# 2_4G.net
KiCad netlist of a schematic drawn in Altium Designer
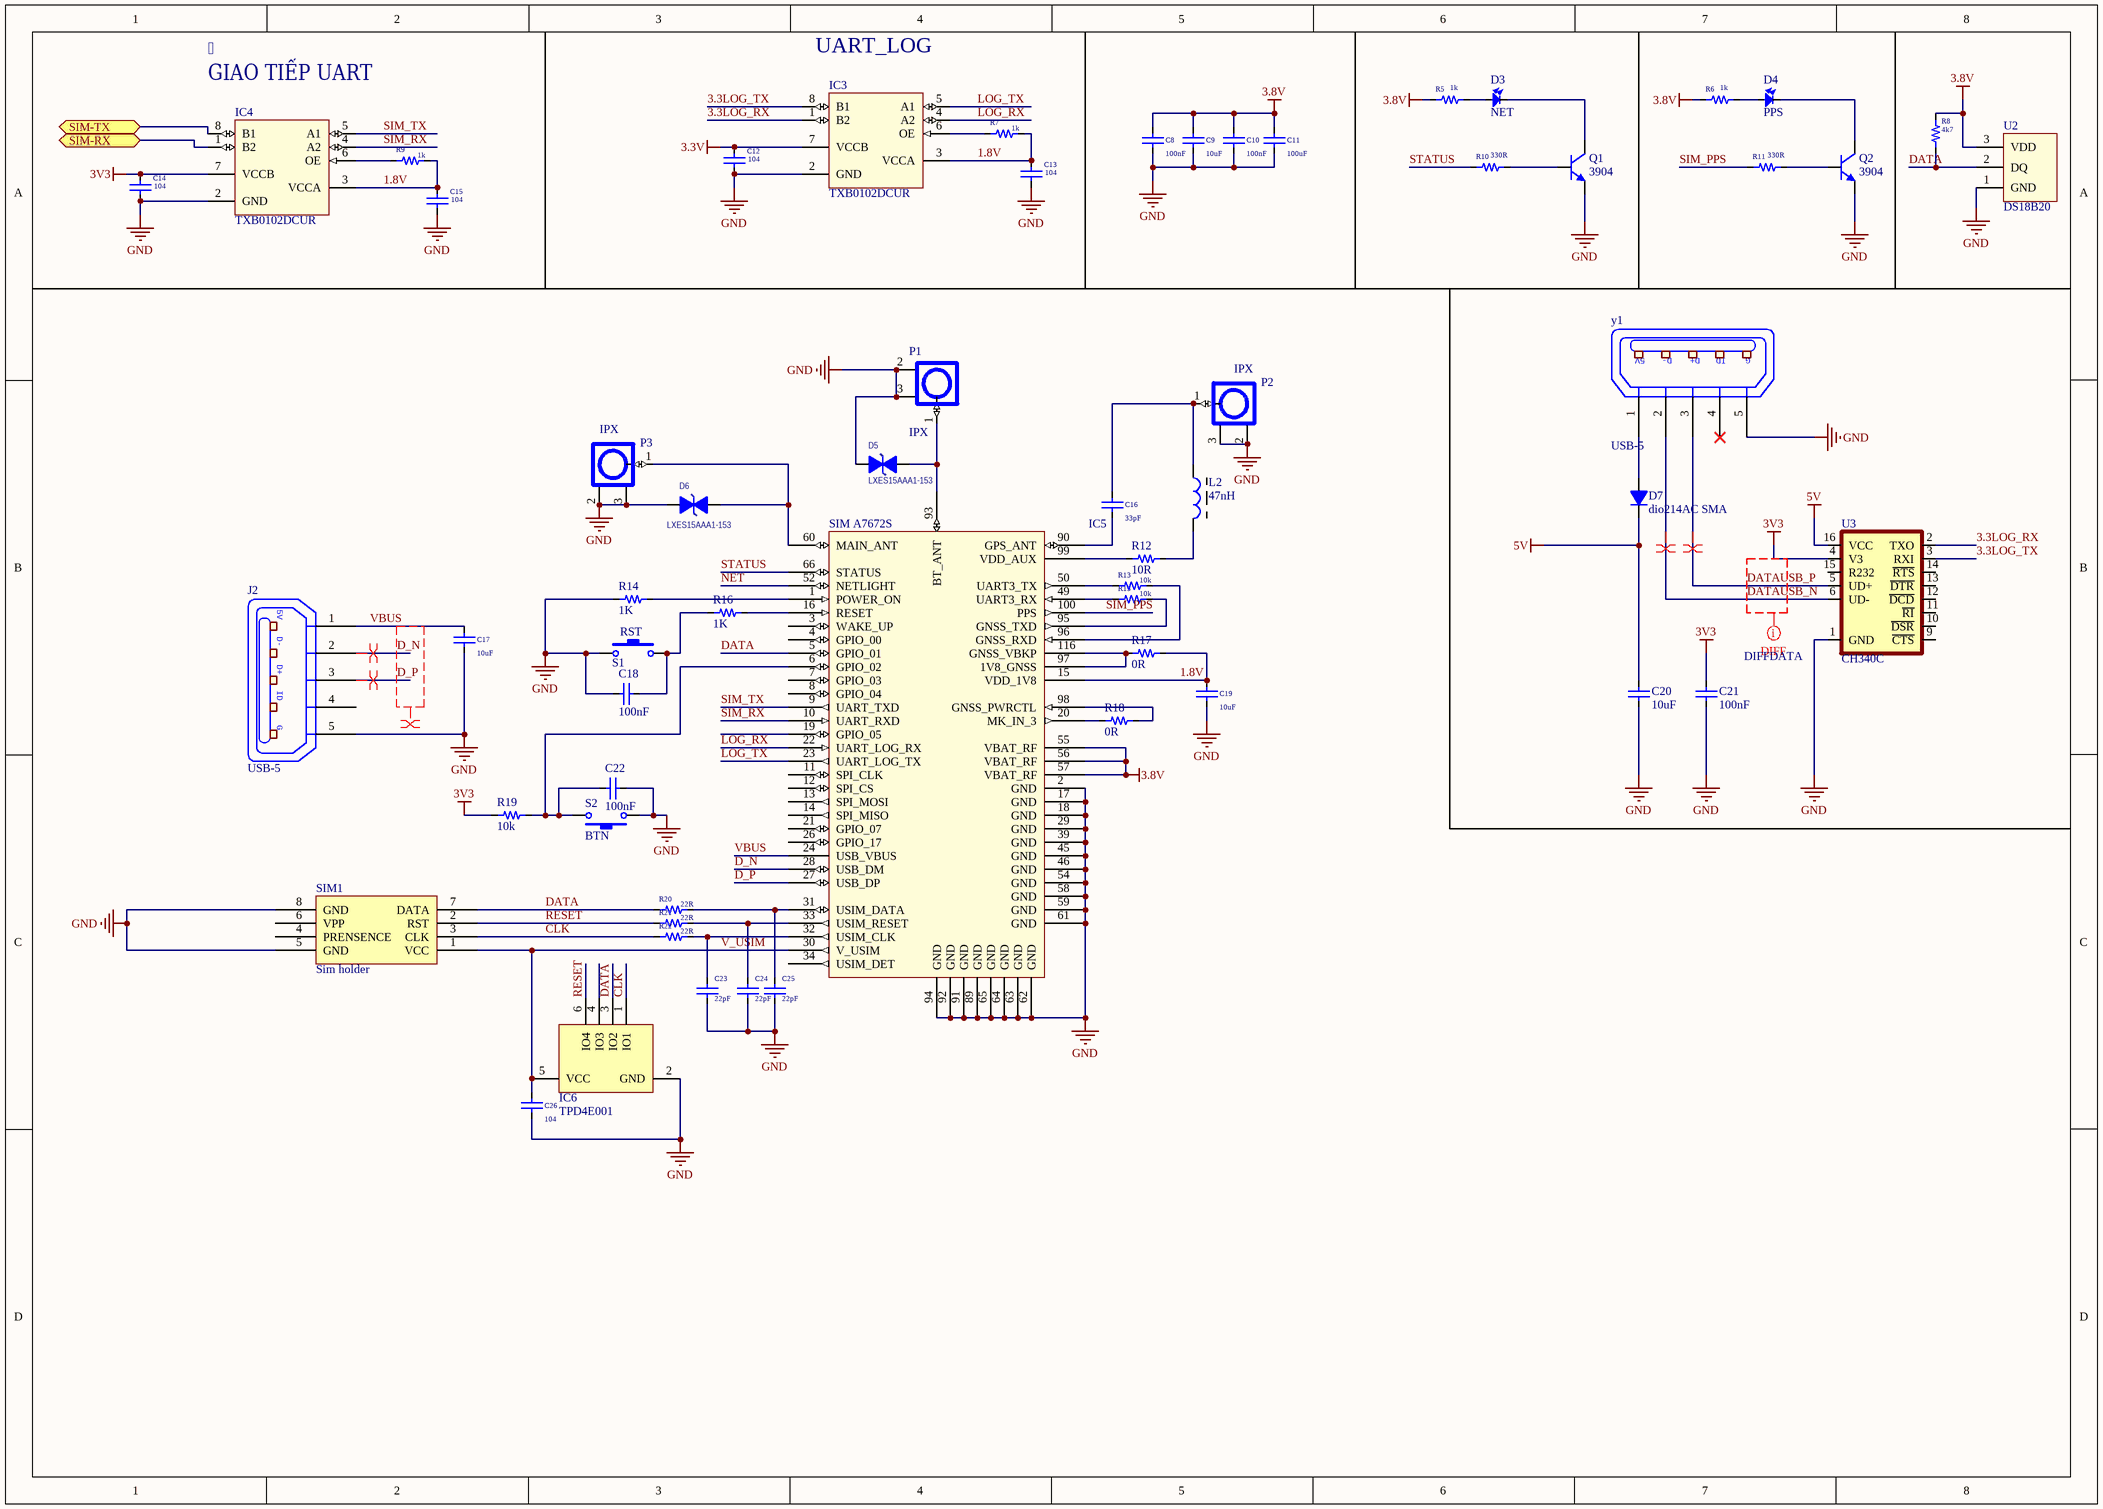
[diagram p0: 2.4G.SchDoc]

(export (version "E")
  (design (tool "Eeschema 10.0.6"))
  (components
    (comp (ref "C8")
      (value "100nF")
      (footprint "CAP_0805")
      (description "Capacitor")
      (fields (field (name "PUBLISHER") "Altium Limited"))
      (libsource (lib "My Library") (part "CapSMD"))
    )
    (comp (ref "C9")
      (value "10uF")
      (footprint "CAP_0805")
      (description "Capacitor")
      (fields (field (name "PUBLISHER") "Altium Limited"))
      (libsource (lib "My Library") (part "CapSMD"))
    )
    (comp (ref "C10")
      (value "100nF")
      (footprint "CAP_0805")
      (description "Capacitor")
      (fields (field (name "PUBLISHER") "Altium Limited"))
      (libsource (lib "My Library") (part "CapSMD"))
    )
    (comp (ref "C11")
      (value "100uF")
      (footprint "CAP_0805")
      (description "Capacitor")
      (fields (field (name "PUBLISHER") "Altium Limited"))
      (libsource (lib "My Library") (part "CapSMD"))
    )
    (comp (ref "C12")
      (value "104")
      (footprint "CAP_0805")
      (description "Capacitor")
      (fields (field (name "PUBLISHER") "Altium Limited"))
      (libsource (lib "My Library") (part "CapSMD"))
    )
    (comp (ref "C13")
      (value "104")
      (footprint "CAP_0805")
      (description "Capacitor")
      (fields (field (name "PUBLISHER") "Altium Limited"))
      (libsource (lib "My Library") (part "CapSMD"))
    )
    (comp (ref "C14")
      (value "104")
      (footprint "CAP_0805")
      (description "Capacitor")
      (fields (field (name "PUBLISHER") "Altium Limited"))
      (libsource (lib "My Library") (part "CapSMD"))
    )
    (comp (ref "C15")
      (value "104")
      (footprint "CAP_0805")
      (description "Capacitor")
      (fields (field (name "PUBLISHER") "Altium Limited"))
      (libsource (lib "My Library") (part "CapSMD"))
    )
    (comp (ref "C16")
      (value "33pF")
      (footprint "CAP_0805")
      (description "Capacitor")
      (fields (field (name "PUBLISHER") "Altium Limited"))
      (libsource (lib "My Library") (part "CapSMD"))
    )
    (comp (ref "C17")
      (value "10uF")
      (footprint "CAP_0603")
      (description "Capacitor")
      (fields (field (name "PUBLISHER") "Altium Limited"))
      (libsource (lib "My Library") (part "CapSMD"))
    )
    (comp (ref "C18")
      (value "100nF")
      (footprint "CAP_0805")
      (description "Capacitor")
      (fields (field (name "PUBLISHER") "Altium Limited"))
      (libsource (lib "My-Library") (part "CapSMD"))
    )
    (comp (ref "C19")
      (value "10uF")
      (footprint "CAP_0805")
      (description "Capacitor")
      (fields (field (name "PUBLISHER") "Altium Limited"))
      (libsource (lib "My Library") (part "CapSMD"))
    )
    (comp (ref "C20")
      (value "10uF")
      (footprint "CAP_0805")
      (description "Capacitor")
      (fields (field (name "PUBLISHER") "Altium Limited"))
      (libsource (lib "Main") (part "CapSMD"))
    )
    (comp (ref "C21")
      (value "100nF")
      (footprint "CAP_0402")
      (description "Capacitor")
      (fields (field (name "PUBLISHER") "Altium Limited"))
      (libsource (lib "Main") (part "CapSMD"))
    )
    (comp (ref "C22")
      (value "100nF")
      (footprint "CAP_0805")
      (description "Capacitor")
      (fields (field (name "PUBLISHER") "Altium Limited"))
      (libsource (lib "My-Library") (part "CapSMD"))
    )
    (comp (ref "C23")
      (value "22pF")
      (footprint "CAP_0805")
      (description "Capacitor")
      (fields (field (name "PUBLISHER") "Altium Limited"))
      (libsource (lib "My Library") (part "CapSMD"))
    )
    (comp (ref "C24")
      (value "22pF")
      (footprint "CAP_0805")
      (description "Capacitor")
      (fields (field (name "PUBLISHER") "Altium Limited"))
      (libsource (lib "My Library") (part "CapSMD"))
    )
    (comp (ref "C25")
      (value "22pF")
      (footprint "CAP_0805")
      (description "Capacitor")
      (fields (field (name "PUBLISHER") "Altium Limited"))
      (libsource (lib "My Library") (part "CapSMD"))
    )
    (comp (ref "C26")
      (value "104")
      (footprint "CAP_0805")
      (description "Capacitor")
      (fields (field (name "PUBLISHER") "Altium Limited"))
      (libsource (lib "My Library") (part "CapSMD"))
    )
    (comp (ref "D3")
      (value "NET")
      (footprint "LED-0805-Blue")
      (description "LED Single colour Green and Red")
      (libsource (lib "My Library") (part "LED"))
    )
    (comp (ref "D4")
      (value "PPS")
      (footprint "LED-0805-Blue")
      (description "LED Single colour Green and Red")
      (libsource (lib "My Library") (part "LED"))
    )
    (comp (ref "D5")
      (value "LXES15AAA1-153")
      (footprint "INDC1005X45")
      (description "TVS DIODE 4VWM 1005")
      (fields (field (name "MANUFACTURER") "Murata Electronics"))
      (libsource (lib "Anh_Trung") (part "TVS"))
    )
    (comp (ref "D6")
      (value "LXES15AAA1-153")
      (footprint "INDC1005X45")
      (description "TVS DIODE 4VWM 1005")
      (fields (field (name "MANUFACTURER") "Murata Electronics"))
      (libsource (lib "Anh_Trung") (part "TVS"))
    )
    (comp (ref "D7")
      (value "dio214AC SMA")
      (footprint "DIO-SMD-106")
      (description "Diode 1A")
      (libsource (lib "Main") (part "D1A"))
    )
    (comp (ref "IC3")
      (value "TXB0102DCUR")
      (footprint "SOP50P310X90-8N")
      (description "IC TRNSLTR BIDIRECTIONAL US8")
      (fields (field (name "MANUFACTURER") "Texas Instruments"))
      (libsource (lib "My Library") (part "TXB0102DCUR"))
    )
    (comp (ref "IC4")
      (value "TXB0102DCUR")
      (footprint "SOP50P310X90-8N")
      (description "IC TRNSLTR BIDIRECTIONAL US8")
      (fields (field (name "MANUFACTURER") "Texas Instruments"))
      (libsource (lib "Main") (part "TXB0102DCUR"))
    )
    (comp (ref "IC5")
      (value "SIM A7672S")
      (footprint "A7672S")
      (description "SIM A7672S-CAT-M1")
      (libsource (lib "My Library") (part "SIM A7672S"))
    )
    (comp (ref "IC6")
      (value "TPD4E001")
      (footprint "SOT23-6")
      (fields (field (name "MANUFACTURER") "Texas Instruments") (field (name "PART NUMBER") "TPD4E001RDBVR"))
      (libsource (lib "Main") (part "TPD4E001_1"))
    )
    (comp (ref "J2")
      (value "USB-5")
      (footprint "USB-M1")
      (fields (field (name "MANUFACTURER") "FCI"))
      (libsource (lib "SIM_devkit") (part "USB-5"))
    )
    (comp (ref "L2")
      (value "47nH")
      (footprint "Inductor_SMD")
      (description "FIXED IND 47NH 300MA 700MOHM SMD")
      (fields (field (name "MANUFACTURER") "Taiyo Yuden") (field (name "PART NUMBER") "HK160847NJ-T"))
      (libsource (lib "Anh_Trung") (part "Inductor Ferit"))
    )
    (comp (ref "P1")
      (value "IPX")
      (footprint "IPXS")
      (description "Antenna GSM GPS")
      (fields
        (field (name "MANUFACTURER") "TE Connectivity AMP Connectors")
        (field (name "PART NUMBER") "2334884-1")
      )
      (libsource (lib "Anh_Trung") (part "IPXSx66"))
    )
    (comp (ref "P2")
      (value "IPX")
      (footprint "IPXS")
      (description "Antenna GSM GPS")
      (fields
        (field (name "MANUFACTURER") "TE Connectivity AMP Connectors")
        (field (name "PART NUMBER") "2334884-1")
      )
      (libsource (lib "") (part "IPXSx66_1"))
    )
    (comp (ref "P3")
      (value "IPX")
      (footprint "IPXS")
      (description "Antenna GSM GPS")
      (fields
        (field (name "MANUFACTURER") "TE Connectivity AMP Connectors")
        (field (name "PART NUMBER") "2334884-1")
      )
      (libsource (lib "Anh_Trung") (part "IPXSx66"))
    )
    (comp (ref "Q1") (value "3904") (footprint "MMBT3904") (libsource (lib "My Library") (part "MMBT3904")))
    (comp (ref "Q2") (value "3904") (footprint "MMBT3904") (libsource (lib "My Library") (part "MMBT3904")))
    (comp (ref "R5")
      (value "1k")
      (footprint "RES-SMD-0805")
      (description "Resistor")
      (fields
        (field (name "MANUFACTURER") "Generic Components")
        (field (name "PUBLISHER") "Altium Hobart Technology Centre")
      )
      (libsource (lib "My Library") (part "Resistor - SMD"))
    )
    (comp (ref "R6")
      (value "1k")
      (footprint "RES-SMD-0805")
      (description "Resistor")
      (fields
        (field (name "MANUFACTURER") "Generic Components")
        (field (name "PUBLISHER") "Altium Hobart Technology Centre")
      )
      (libsource (lib "My Library") (part "Resistor - SMD"))
    )
    (comp (ref "R7")
      (value "1k")
      (footprint "RES-SMD-0805")
      (description "Resistor")
      (fields
        (field (name "MANUFACTURER") "Generic Components")
        (field (name "PUBLISHER") "Altium Hobart Technology Centre")
      )
      (libsource (lib "My Library") (part "Resistor - SMD"))
    )
    (comp (ref "R8")
      (value "4k7")
      (footprint "RES-SMD-0805")
      (description "Resistor")
      (fields
        (field (name "MANUFACTURER") "Generic Components")
        (field (name "PUBLISHER") "Altium Hobart Technology Centre")
      )
      (libsource (lib "My Library") (part "Resistor - SMD"))
    )
    (comp (ref "R9")
      (value "1k")
      (footprint "RES-SMD-0805")
      (description "Resistor")
      (fields
        (field (name "MANUFACTURER") "Generic Components")
        (field (name "PUBLISHER") "Altium Hobart Technology Centre")
      )
      (libsource (lib "My Library") (part "Resistor - SMD"))
    )
    (comp (ref "R10")
      (value "330R")
      (footprint "RES-SMD-0805")
      (description "Resistor")
      (fields
        (field (name "MANUFACTURER") "Generic Components")
        (field (name "PUBLISHER") "Altium Hobart Technology Centre")
      )
      (libsource (lib "My Library") (part "Resistor - SMD"))
    )
    (comp (ref "R11")
      (value "330R")
      (footprint "RES-SMD-0805")
      (description "Resistor")
      (fields
        (field (name "MANUFACTURER") "Generic Components")
        (field (name "PUBLISHER") "Altium Hobart Technology Centre")
      )
      (libsource (lib "My Library") (part "Resistor - SMD"))
    )
    (comp (ref "R12")
      (value "10R")
      (footprint "RES-SMD-0805")
      (description "Resistor")
      (fields
        (field (name "MANUFACTURER") "Generic Components")
        (field (name "PUBLISHER") "Altium Hobart Technology Centre")
      )
      (libsource (lib "My Library") (part "Resistor - SMD"))
    )
    (comp (ref "R13")
      (value "10k")
      (footprint "RES-SMD-0805")
      (description "Resistor")
      (fields
        (field (name "MANUFACTURER") "Generic Components")
        (field (name "PUBLISHER") "Altium Hobart Technology Centre")
      )
      (libsource (lib "My Library") (part "Resistor - SMD"))
    )
    (comp (ref "R14")
      (value "1K")
      (footprint "RES-SMD-0805")
      (description "Resistor")
      (fields
        (field (name "MANUFACTURER") "Generic Components")
        (field (name "PUBLISHER") "Altium Hobart Technology Centre")
      )
      (libsource (lib "My Library") (part "Resistor - SMD"))
    )
    (comp (ref "R15")
      (value "10k")
      (footprint "RES-SMD-0805")
      (description "Resistor")
      (fields
        (field (name "MANUFACTURER") "Generic Components")
        (field (name "PUBLISHER") "Altium Hobart Technology Centre")
      )
      (libsource (lib "My Library") (part "Resistor - SMD"))
    )
    (comp (ref "R16")
      (value "1K")
      (footprint "RES-SMD-0805")
      (description "Resistor")
      (fields
        (field (name "MANUFACTURER") "Generic Components")
        (field (name "PUBLISHER") "Altium Hobart Technology Centre")
      )
      (libsource (lib "My Library") (part "Resistor - SMD"))
    )
    (comp (ref "R17")
      (value "0R")
      (footprint "RES-SMD-0805")
      (description "Resistor")
      (fields
        (field (name "MANUFACTURER") "Generic Components")
        (field (name "PUBLISHER") "Altium Hobart Technology Centre")
      )
      (libsource (lib "My Library") (part "Resistor - SMD"))
    )
    (comp (ref "R18")
      (value "0R")
      (footprint "RES-SMD-0805")
      (description "Resistor")
      (fields
        (field (name "MANUFACTURER") "Generic Components")
        (field (name "PUBLISHER") "Altium Hobart Technology Centre")
      )
      (libsource (lib "My Library") (part "Resistor - SMD"))
    )
    (comp (ref "R19")
      (value "10k")
      (footprint "RES-SMD-0805")
      (description "Resistor")
      (fields
        (field (name "MANUFACTURER") "Generic Components")
        (field (name "PUBLISHER") "Altium Hobart Technology Centre")
      )
      (libsource (lib "My Library") (part "Resistor - SMD"))
    )
    (comp (ref "R20")
      (value "22R")
      (footprint "RES-SMD-0805")
      (description "Resistor")
      (fields
        (field (name "MANUFACTURER") "Generic Components")
        (field (name "PUBLISHER") "Altium Hobart Technology Centre")
      )
      (libsource (lib "My Library") (part "Resistor - SMD"))
    )
    (comp (ref "R21")
      (value "22R")
      (footprint "RES-SMD-0805")
      (description "Resistor")
      (fields
        (field (name "MANUFACTURER") "Generic Components")
        (field (name "PUBLISHER") "Altium Hobart Technology Centre")
      )
      (libsource (lib "My Library") (part "Resistor - SMD"))
    )
    (comp (ref "R22")
      (value "22R")
      (footprint "RES-SMD-0805")
      (description "Resistor")
      (fields
        (field (name "MANUFACTURER") "Generic Components")
        (field (name "PUBLISHER") "Altium Hobart Technology Centre")
      )
      (libsource (lib "My Library") (part "Resistor - SMD"))
    )
    (comp (ref "S1")
      (value "RST")
      (footprint "SW-SMD")
      (description "Switch")
      (fields (field (name "PUBLISHER") "Altium Limited"))
      (libsource (lib "My Library") (part "SW-SMD"))
    )
    (comp (ref "S2")
      (value "BTN")
      (footprint "SW-SMD")
      (description "Switch")
      (fields (field (name "PUBLISHER") "Altium Limited"))
      (libsource (lib "My Library") (part "SW-SMD"))
    )
    (comp (ref "SIM1")
      (value "Sim holder")
      (footprint "SIM_MicroSIM 6P Flip")
      (libsource (lib "My-Library") (part "SIM_MicroSim"))
    )
    (comp (ref "U2")
      (value "DS18B20")
      (footprint "QTO-92A")
      (description "High Precision  1-Wire® Digital Thermometer")
      (libsource (lib "Main") (part "DS18B20"))
    )
    (comp (ref "U3")
      (value "CH340C")
      (footprint "SOP-16")
      (description "USB to serial chip CH340")
      (fields (field (name "MF") "WCH"))
      (libsource (lib "Main") (part "CH340C"))
    )
    (comp (ref "y1")
      (value "USB-5")
      (footprint "USB-M1")
      (fields (field (name "MANUFACTURER") "FCI"))
      (libsource (lib "") (part "USB-5_1"))
    )
  )
  (nets
    (net (code "1") (name "/1.8V") (class "Default")
      (node (ref "C13") (pin "2") (pinfunction "2_2") (pintype "passive"))
      (node (ref "C15") (pin "2") (pinfunction "2_2") (pintype "passive"))
      (node (ref "C19") (pin "2") (pinfunction "2_2") (pintype "passive"))
      (node (ref "IC3") (pin "3") (pinfunction "VCCA_3") (pintype "power_in"))
      (node (ref "IC4") (pin "3") (pinfunction "VCCA_3") (pintype "power_in"))
      (node (ref "IC5") (pin "15") (pinfunction "VDD_1V8_15") (pintype "passive"))
      (node (ref "R17") (pin "2") (pinfunction "2_2") (pintype "passive"))
      (node (ref "R7") (pin "1") (pinfunction "1_1") (pintype "passive"))
      (node (ref "R9") (pin "1") (pinfunction "1_1") (pintype "passive"))
    )
    (net (code "2") (name "/3.3LOG_RX") (class "Default")
      (node (ref "IC3") (pin "1") (pinfunction "B2_1") (pintype "bidirectional"))
      (node (ref "U3") (pin "2") (pinfunction "TXO_2") (pintype "bidirectional"))
    )
    (net (code "3") (name "/3.3LOG_TX") (class "Default")
      (node (ref "IC3") (pin "8") (pinfunction "B1_8") (pintype "bidirectional"))
      (node (ref "U3") (pin "3") (pinfunction "RXI_3") (pintype "bidirectional"))
    )
    (net (code "4") (name "/CLK") (class "Default")
      (node (ref "IC6") (pin "1") (pinfunction "IO1_1") (pintype "passive"))
      (node (ref "R22") (pin "2") (pinfunction "2_2") (pintype "passive"))
      (node (ref "SIM1") (pin "3") (pinfunction "CLK_3") (pintype "passive"))
    )
    (net (code "5") (name "/DATA") (class "Default")
      (node (ref "IC5") (pin "5") (pinfunction "GPIO_01_5") (pintype "bidirectional"))
      (node (ref "IC6") (pin "3") (pinfunction "IO2_3") (pintype "passive"))
      (node (ref "R20") (pin "2") (pinfunction "2_2") (pintype "passive"))
      (node (ref "R8") (pin "2") (pinfunction "2_2") (pintype "passive"))
      (node (ref "SIM1") (pin "7") (pinfunction "DATA_7") (pintype "passive"))
      (node (ref "U2") (pin "2") (pinfunction "DQ_2") (pintype "passive"))
    )
    (net (code "6") (name "/DATAUSB_N") (class "Default")
      (node (ref "U3") (pin "6") (pinfunction "UD-_6") (pintype "bidirectional"))
      (node (ref "y1") (pin "2") (pinfunction "P2_2") (pintype "passive"))
    )
    (net (code "7") (name "/DATAUSB_P") (class "Default")
      (node (ref "U3") (pin "5") (pinfunction "UD+_5") (pintype "bidirectional"))
      (node (ref "y1") (pin "3") (pinfunction "P3_3") (pintype "passive"))
    )
    (net (code "8") (name "/D_N") (class "Default")
      (node (ref "IC5") (pin "28") (pinfunction "USB_DM_28") (pintype "bidirectional"))
      (node (ref "J2") (pin "2") (pinfunction "P2_2") (pintype "passive"))
    )
    (net (code "9") (name "/D_P") (class "Default")
      (node (ref "IC5") (pin "27") (pinfunction "USB_DP_27") (pintype "bidirectional"))
      (node (ref "J2") (pin "3") (pinfunction "P3_3") (pintype "passive"))
    )
    (net (code "10") (name "/LOG_RX") (class "Default")
      (node (ref "IC3") (pin "4") (pinfunction "A2_4") (pintype "bidirectional"))
      (node (ref "IC5") (pin "22") (pinfunction "UART_LOG_RX_22") (pintype "input"))
    )
    (net (code "11") (name "/LOG_TX") (class "Default")
      (node (ref "IC3") (pin "5") (pinfunction "A1_5") (pintype "bidirectional"))
      (node (ref "IC5") (pin "23") (pinfunction "UART_LOG_TX_23") (pintype "output"))
    )
    (net (code "12") (name "/NET") (class "Default")
      (node (ref "IC5") (pin "52") (pinfunction "NETLIGHT_52") (pintype "bidirectional"))
    )
    (net (code "13") (name "/RESET") (class "Default")
      (node (ref "IC6") (pin "6") (pinfunction "IO4_6") (pintype "passive"))
      (node (ref "R21") (pin "2") (pinfunction "2_2") (pintype "passive"))
      (node (ref "SIM1") (pin "2") (pinfunction "RST_2") (pintype "passive"))
    )
    (net (code "14") (name "/SIM-RX") (class "Default")
      (node (ref "IC4") (pin "1") (pinfunction "B2_1") (pintype "bidirectional"))
    )
    (net (code "15") (name "/SIM-TX") (class "Default")
      (node (ref "IC4") (pin "8") (pinfunction "B1_8") (pintype "bidirectional"))
    )
    (net (code "16") (name "/SIM_PPS") (class "Default")
      (node (ref "IC5") (pin "100") (pinfunction "PPS_100") (pintype "output"))
      (node (ref "R11") (pin "2") (pinfunction "2_2") (pintype "passive"))
    )
    (net (code "17") (name "/SIM_RX") (class "Default")
      (node (ref "IC4") (pin "4") (pinfunction "A2_4") (pintype "bidirectional"))
      (node (ref "IC5") (pin "10") (pinfunction "UART_RXD_10") (pintype "input"))
    )
    (net (code "18") (name "/SIM_TX") (class "Default")
      (node (ref "IC4") (pin "5") (pinfunction "A1_5") (pintype "bidirectional"))
      (node (ref "IC5") (pin "9") (pinfunction "UART_TXD_9") (pintype "output"))
    )
    (net (code "19") (name "/STATUS") (class "Default")
      (node (ref "IC5") (pin "66") (pinfunction "STATUS_66") (pintype "bidirectional"))
      (node (ref "R10") (pin "2") (pinfunction "2_2") (pintype "passive"))
    )
    (net (code "20") (name "/VBUS") (class "Default")
      (node (ref "C17") (pin "2") (pinfunction "2_2") (pintype "passive"))
      (node (ref "IC5") (pin "24") (pinfunction "USB_VBUS_24") (pintype "passive"))
      (node (ref "J2") (pin "1") (pinfunction "P1_1") (pintype "passive"))
    )
    (net (code "21") (name "/V_USIM") (class "Default")
      (node (ref "C26") (pin "2") (pinfunction "2_2") (pintype "passive"))
      (node (ref "IC5") (pin "30") (pinfunction "V_USIM_30") (pintype "output"))
      (node (ref "IC6") (pin "5") (pinfunction "VCC_5") (pintype "passive"))
      (node (ref "SIM1") (pin "1") (pinfunction "VCC_1") (pintype "passive"))
    )
    (net (code "22") (name "3.3V") (class "Default")
      (node (ref "C12") (pin "2") (pinfunction "2_2") (pintype "passive"))
      (node (ref "IC3") (pin "7") (pinfunction "VCCB_7") (pintype "power_in"))
    )
    (net (code "23") (name "3.8V") (class "Default")
      (node (ref "C10") (pin "2") (pinfunction "2_2") (pintype "passive"))
      (node (ref "C11") (pin "2") (pinfunction "2_2") (pintype "passive"))
      (node (ref "C8") (pin "2") (pinfunction "2_2") (pintype "passive"))
      (node (ref "C9") (pin "2") (pinfunction "2_2") (pintype "passive"))
      (node (ref "IC5") (pin "55") (pinfunction "VBAT_RF_55") (pintype "passive"))
      (node (ref "IC5") (pin "56") (pinfunction "VBAT_RF_56") (pintype "passive"))
      (node (ref "IC5") (pin "57") (pinfunction "VBAT_RF_57") (pintype "passive"))
      (node (ref "R5") (pin "2") (pinfunction "2_2") (pintype "passive"))
      (node (ref "R6") (pin "2") (pinfunction "2_2") (pintype "passive"))
      (node (ref "R8") (pin "1") (pinfunction "1_1") (pintype "passive"))
      (node (ref "U2") (pin "3") (pinfunction "VDD_3") (pintype "passive"))
    )
    (net (code "24") (name "3V3") (class "Default")
      (node (ref "C14") (pin "2") (pinfunction "2_2") (pintype "passive"))
      (node (ref "C21") (pin "1") (pinfunction "1_1") (pintype "passive"))
      (node (ref "IC4") (pin "7") (pinfunction "VCCB_7") (pintype "power_in"))
      (node (ref "R19") (pin "1") (pinfunction "1_1") (pintype "passive"))
      (node (ref "U3") (pin "4") (pinfunction "V3_4") (pintype "bidirectional"))
    )
    (net (code "25") (name "5V") (class "Default")
      (node (ref "C20") (pin "1") (pinfunction "1_1") (pintype "passive"))
      (node (ref "D7") (pin "2") (pinfunction "K_2") (pintype "passive"))
      (node (ref "U3") (pin "16") (pinfunction "VCC_16") (pintype "bidirectional"))
    )
    (net (code "26") (name "GND") (class "Default")
      (node (ref "C10") (pin "1") (pinfunction "1_1") (pintype "passive"))
      (node (ref "C11") (pin "1") (pinfunction "1_1") (pintype "passive"))
      (node (ref "C12") (pin "1") (pinfunction "1_1") (pintype "passive"))
      (node (ref "C13") (pin "1") (pinfunction "1_1") (pintype "passive"))
      (node (ref "C14") (pin "1") (pinfunction "1_1") (pintype "passive"))
      (node (ref "C15") (pin "1") (pinfunction "1_1") (pintype "passive"))
      (node (ref "C17") (pin "1") (pinfunction "1_1") (pintype "passive"))
      (node (ref "C18") (pin "1") (pinfunction "1_1") (pintype "passive"))
      (node (ref "C19") (pin "1") (pinfunction "1_1") (pintype "passive"))
      (node (ref "C20") (pin "2") (pinfunction "2_2") (pintype "passive"))
      (node (ref "C21") (pin "2") (pinfunction "2_2") (pintype "passive"))
      (node (ref "C22") (pin "2") (pinfunction "2_2") (pintype "passive"))
      (node (ref "C23") (pin "1") (pinfunction "1_1") (pintype "passive"))
      (node (ref "C24") (pin "1") (pinfunction "1_1") (pintype "passive"))
      (node (ref "C25") (pin "1") (pinfunction "1_1") (pintype "passive"))
      (node (ref "C26") (pin "1") (pinfunction "1_1") (pintype "passive"))
      (node (ref "C8") (pin "1") (pinfunction "1_1") (pintype "passive"))
      (node (ref "C9") (pin "1") (pinfunction "1_1") (pintype "passive"))
      (node (ref "D5") (pin "2") (pinfunction "K_2") (pintype "passive"))
      (node (ref "D6") (pin "2") (pinfunction "K_2") (pintype "passive"))
      (node (ref "IC3") (pin "2") (pinfunction "GND_2") (pintype "power_in"))
      (node (ref "IC4") (pin "2") (pinfunction "GND_2") (pintype "power_in"))
      (node (ref "IC5") (pin "17") (pinfunction "GND_17") (pintype "passive"))
      (node (ref "IC5") (pin "18") (pinfunction "GND_18") (pintype "passive"))
      (node (ref "IC5") (pin "2") (pinfunction "GND_2") (pintype "passive"))
      (node (ref "IC5") (pin "29") (pinfunction "GND_29") (pintype "passive"))
      (node (ref "IC5") (pin "39") (pinfunction "GND_39") (pintype "passive"))
      (node (ref "IC5") (pin "45") (pinfunction "GND_45") (pintype "passive"))
      (node (ref "IC5") (pin "46") (pinfunction "GND_46") (pintype "passive"))
      (node (ref "IC5") (pin "54") (pinfunction "GND_54") (pintype "passive"))
      (node (ref "IC5") (pin "58") (pinfunction "GND_58") (pintype "passive"))
      (node (ref "IC5") (pin "59") (pinfunction "GND_59") (pintype "passive"))
      (node (ref "IC5") (pin "61") (pinfunction "GND_61") (pintype "passive"))
      (node (ref "IC5") (pin "62") (pinfunction "GND_62") (pintype "passive"))
      (node (ref "IC5") (pin "63") (pinfunction "GND_63") (pintype "passive"))
      (node (ref "IC5") (pin "64") (pinfunction "GND_64") (pintype "passive"))
      (node (ref "IC5") (pin "65") (pinfunction "GND_65") (pintype "passive"))
      (node (ref "IC5") (pin "89") (pinfunction "GND_89") (pintype "passive"))
      (node (ref "IC5") (pin "91") (pinfunction "GND_91") (pintype "passive"))
      (node (ref "IC5") (pin "92") (pinfunction "GND_92") (pintype "passive"))
      (node (ref "IC5") (pin "94") (pinfunction "GND_94") (pintype "passive"))
      (node (ref "IC6") (pin "2") (pinfunction "GND_2") (pintype "passive"))
      (node (ref "J2") (pin "5") (pinfunction "P5_5") (pintype "passive"))
      (node (ref "P1") (pin "2") (pintype "passive"))
      (node (ref "P1") (pin "3") (pintype "passive"))
      (node (ref "P2") (pin "2") (pintype "passive"))
      (node (ref "P2") (pin "3") (pintype "passive"))
      (node (ref "P3") (pin "2") (pintype "passive"))
      (node (ref "P3") (pin "3") (pintype "passive"))
      (node (ref "Q1") (pin "2") (pinfunction "E_2") (pintype "passive"))
      (node (ref "Q2") (pin "2") (pinfunction "E_2") (pintype "passive"))
      (node (ref "R14") (pin "1") (pinfunction "1_1") (pintype "passive"))
      (node (ref "S1") (pin "1") (pinfunction "1_1") (pintype "passive"))
      (node (ref "S2") (pin "1") (pinfunction "1_1") (pintype "passive"))
      (node (ref "SIM1") (pin "5") (pinfunction "GND_5") (pintype "passive"))
      (node (ref "SIM1") (pin "8") (pinfunction "GND_8") (pintype "passive"))
      (node (ref "U2") (pin "1") (pinfunction "GND_1") (pintype "passive"))
      (node (ref "U3") (pin "1") (pinfunction "GND_1") (pintype "bidirectional"))
      (node (ref "y1") (pin "5") (pinfunction "P5_5") (pintype "passive"))
    )
    (net (code "27") (name "Net-(C16-Pad2)") (class "Default")
      (node (ref "C16") (pin "2") (pinfunction "2_2") (pintype "passive"))
      (node (ref "L2") (pin "1") (pinfunction "1_1") (pintype "passive"))
      (node (ref "P2") (pin "1") (pintype "bidirectional"))
    )
    (net (code "28") (name "Net-(C18-Pad2)") (class "Default")
      (node (ref "C18") (pin "2") (pinfunction "2_2") (pintype "passive"))
      (node (ref "R16") (pin "1") (pinfunction "1_1") (pintype "passive"))
      (node (ref "S1") (pin "2") (pinfunction "2_2") (pintype "passive"))
    )
    (net (code "29") (name "Net-(D3-Pad1)") (class "Default")
      (node (ref "D3") (pin "1") (pinfunction "1_1") (pintype "passive"))
      (node (ref "R5") (pin "1") (pinfunction "1_1") (pintype "passive"))
    )
    (net (code "30") (name "Net-(D4-Pad1)") (class "Default")
      (node (ref "D4") (pin "1") (pinfunction "1_1") (pintype "passive"))
      (node (ref "R6") (pin "1") (pinfunction "1_1") (pintype "passive"))
    )
    (net (code "31") (name "Net-(D5-A)") (class "Default")
      (node (ref "D5") (pin "1") (pinfunction "A_1") (pintype "passive"))
      (node (ref "IC5") (pin "93") (pinfunction "BT_ANT_93") (pintype "bidirectional"))
      (node (ref "P1") (pin "1") (pintype "bidirectional"))
    )
    (net (code "32") (name "Net-(D6-A)") (class "Default")
      (node (ref "D6") (pin "1") (pinfunction "A_1") (pintype "passive"))
      (node (ref "IC5") (pin "60") (pinfunction "MAIN_ANT_60") (pintype "bidirectional"))
      (node (ref "P3") (pin "1") (pintype "bidirectional"))
    )
    (net (code "33") (name "Net-(D7-A)") (class "Default")
      (node (ref "D7") (pin "1") (pinfunction "A_1") (pintype "passive"))
      (node (ref "y1") (pin "1") (pinfunction "P1_1") (pintype "passive"))
    )
    (net (code "34") (name "Net-(IC3-OE)") (class "Default")
      (node (ref "IC3") (pin "6") (pinfunction "OE_6") (pintype "input"))
      (node (ref "R7") (pin "2") (pinfunction "2_2") (pintype "passive"))
    )
    (net (code "35") (name "Net-(IC4-OE)") (class "Default")
      (node (ref "IC4") (pin "6") (pinfunction "OE_6") (pintype "input"))
      (node (ref "R9") (pin "2") (pinfunction "2_2") (pintype "passive"))
    )
    (net (code "36") (name "Net-(IC5-1V8_GNSS)") (class "Default")
      (node (ref "IC5") (pin "116") (pinfunction "GNSS_VBKP_116") (pintype "passive"))
      (node (ref "IC5") (pin "97") (pinfunction "1V8_GNSS_97") (pintype "passive"))
      (node (ref "R17") (pin "1") (pinfunction "1_1") (pintype "passive"))
    )
    (net (code "37") (name "Net-(IC5-GNSS_PWRCTL)") (class "Default")
      (node (ref "IC5") (pin "98") (pinfunction "GNSS_PWRCTL_98") (pintype "input"))
      (node (ref "R18") (pin "2") (pinfunction "2_2") (pintype "passive"))
    )
    (net (code "38") (name "Net-(IC5-GNSS_RXD)") (class "Default")
      (node (ref "IC5") (pin "96") (pinfunction "GNSS_RXD_96") (pintype "input"))
      (node (ref "R13") (pin "1") (pinfunction "1_1") (pintype "passive"))
    )
    (net (code "39") (name "Net-(IC5-GNSS_TXD)") (class "Default")
      (node (ref "IC5") (pin "95") (pinfunction "GNSS_TXD_95") (pintype "output"))
      (node (ref "R15") (pin "1") (pinfunction "1_1") (pintype "passive"))
    )
    (net (code "40") (name "Net-(IC5-GPIO_02)") (class "Default")
      (node (ref "C22") (pin "1") (pinfunction "1_1") (pintype "passive"))
      (node (ref "IC5") (pin "6") (pinfunction "GPIO_02_6") (pintype "bidirectional"))
      (node (ref "R19") (pin "2") (pinfunction "2_2") (pintype "passive"))
      (node (ref "S2") (pin "2") (pinfunction "2_2") (pintype "passive"))
    )
    (net (code "41") (name "Net-(IC5-GPS_ANT)") (class "Default")
      (node (ref "C16") (pin "1") (pinfunction "1_1") (pintype "passive"))
      (node (ref "IC5") (pin "90") (pinfunction "GPS_ANT_90") (pintype "bidirectional"))
    )
    (net (code "42") (name "Net-(IC5-MK_IN_3)") (class "Default")
      (node (ref "IC5") (pin "20") (pinfunction "MK_IN_3_20") (pintype "output"))
      (node (ref "R18") (pin "1") (pinfunction "1_1") (pintype "passive"))
    )
    (net (code "43") (name "Net-(IC5-POWER_ON)") (class "Default")
      (node (ref "IC5") (pin "1") (pinfunction "POWER_ON_1") (pintype "input"))
      (node (ref "R14") (pin "2") (pinfunction "2_2") (pintype "passive"))
    )
    (net (code "44") (name "Net-(IC5-RESET)") (class "Default")
      (node (ref "IC5") (pin "16") (pinfunction "RESET_16") (pintype "input"))
      (node (ref "R16") (pin "2") (pinfunction "2_2") (pintype "passive"))
    )
    (net (code "45") (name "Net-(IC5-UART3_RX)") (class "Default")
      (node (ref "IC5") (pin "49") (pinfunction "UART3_RX_49") (pintype "input"))
      (node (ref "R15") (pin "2") (pinfunction "2_2") (pintype "passive"))
    )
    (net (code "46") (name "Net-(IC5-UART3_TX)") (class "Default")
      (node (ref "IC5") (pin "50") (pinfunction "UART3_TX_50") (pintype "output"))
      (node (ref "R13") (pin "2") (pinfunction "2_2") (pintype "passive"))
    )
    (net (code "47") (name "Net-(IC5-USIM_CLK)") (class "Default")
      (node (ref "C23") (pin "2") (pinfunction "2_2") (pintype "passive"))
      (node (ref "IC5") (pin "32") (pinfunction "USIM_CLK_32") (pintype "output"))
      (node (ref "R22") (pin "1") (pinfunction "1_1") (pintype "passive"))
    )
    (net (code "48") (name "Net-(IC5-USIM_DATA)") (class "Default")
      (node (ref "C25") (pin "2") (pinfunction "2_2") (pintype "passive"))
      (node (ref "IC5") (pin "31") (pinfunction "USIM_DATA_31") (pintype "bidirectional"))
      (node (ref "R20") (pin "1") (pinfunction "1_1") (pintype "passive"))
    )
    (net (code "49") (name "Net-(IC5-USIM_RESET)") (class "Default")
      (node (ref "C24") (pin "2") (pinfunction "2_2") (pintype "passive"))
      (node (ref "IC5") (pin "33") (pinfunction "USIM_RESET_33") (pintype "output"))
      (node (ref "R21") (pin "1") (pinfunction "1_1") (pintype "passive"))
    )
    (net (code "50") (name "Net-(IC5-VDD_AUX)") (class "Default")
      (node (ref "IC5") (pin "99") (pinfunction "VDD_AUX_99") (pintype "passive"))
      (node (ref "R12") (pin "1") (pinfunction "1_1") (pintype "passive"))
    )
    (net (code "51") (name "Net-(L2-Pad2)") (class "Default")
      (node (ref "L2") (pin "2") (pinfunction "2_2") (pintype "passive"))
      (node (ref "R12") (pin "2") (pinfunction "2_2") (pintype "passive"))
    )
    (net (code "52") (name "Net-(Q1-B)") (class "Default")
      (node (ref "Q1") (pin "1") (pinfunction "B_1") (pintype "passive"))
      (node (ref "R10") (pin "1") (pinfunction "1_1") (pintype "passive"))
    )
    (net (code "53") (name "Net-(Q1-C)") (class "Default")
      (node (ref "D3") (pin "2") (pinfunction "2_2") (pintype "passive"))
      (node (ref "Q1") (pin "3") (pinfunction "C_3") (pintype "passive"))
    )
    (net (code "54") (name "Net-(Q2-B)") (class "Default")
      (node (ref "Q2") (pin "1") (pinfunction "B_1") (pintype "passive"))
      (node (ref "R11") (pin "1") (pinfunction "1_1") (pintype "passive"))
    )
    (net (code "55") (name "Net-(Q2-C)") (class "Default")
      (node (ref "D4") (pin "2") (pinfunction "2_2") (pintype "passive"))
      (node (ref "Q2") (pin "3") (pinfunction "C_3") (pintype "passive"))
    )
    (net (code "56") (name "unconnected-(IC5-ADC1-Pad47)") (class "Default")
      (node (ref "IC5") (pin "47") (pinfunction "ADC1_47") (pintype "passive"))
    )
    (net (code "57") (name "unconnected-(IC5-ADC2-Pad46)") (class "Default")
      (node (ref "IC5") (pin "46") (pinfunction "ADC2_46") (pintype "passive"))
    )
    (net (code "58") (name "unconnected-(IC5-EAR1N-Pad25)") (class "Default")
      (node (ref "IC5") (pin "25") (pinfunction "EAR1N_25") (pintype "passive"))
    )
    (net (code "59") (name "unconnected-(IC5-EAR1P-Pad26)") (class "Default")
      (node (ref "IC5") (pin "26") (pinfunction "EAR1P_26") (pintype "passive"))
    )
    (net (code "60") (name "unconnected-(IC5-GPIO1-Pad51)") (class "Default")
      (node (ref "IC5") (pin "51") (pinfunction "GPIO1_51") (pintype "passive"))
    )
    (net (code "61") (name "unconnected-(IC5-GPIO4-Pad54)") (class "Default")
      (node (ref "IC5") (pin "54") (pinfunction "GPIO4_54") (pintype "passive"))
    )
    (net (code "62") (name "unconnected-(IC5-GPIO40-Pad49)") (class "Default")
      (node (ref "IC5") (pin "49") (pinfunction "GPIO40_49") (pintype "passive"))
    )
    (net (code "63") (name "unconnected-(IC5-GPIO41-Pad52)") (class "Default")
      (node (ref "IC5") (pin "52") (pinfunction "GPIO41_52") (pintype "passive"))
    )
    (net (code "64") (name "unconnected-(IC5-GPIO42-Pad53)") (class "Default")
      (node (ref "IC5") (pin "53") (pinfunction "GPIO42_53") (pintype "passive"))
    )
    (net (code "65") (name "unconnected-(IC5-GPIO43-Pad50)") (class "Default")
      (node (ref "IC5") (pin "50") (pinfunction "GPIO43_50") (pintype "passive"))
    )
    (net (code "66") (name "unconnected-(IC5-GPIO44-Pad48)") (class "Default")
      (node (ref "IC5") (pin "48") (pinfunction "GPIO44_48") (pintype "passive"))
    )
    (net (code "67") (name "unconnected-(IC5-GPIO_00-Pad4)") (class "Default")
      (node (ref "IC5") (pin "4") (pinfunction "GPIO_00_4") (pintype "bidirectional"))
    )
    (net (code "68") (name "unconnected-(IC5-GPIO_03-Pad7)") (class "Default")
      (node (ref "IC5") (pin "7") (pinfunction "GPIO_03_7") (pintype "bidirectional"))
    )
    (net (code "69") (name "unconnected-(IC5-GPIO_04-Pad8)") (class "Default")
      (node (ref "IC5") (pin "8") (pinfunction "GPIO_04_8") (pintype "bidirectional"))
    )
    (net (code "70") (name "unconnected-(IC5-GPIO_05-Pad19)") (class "Default")
      (node (ref "IC5") (pin "19") (pinfunction "GPIO_05_19") (pintype "bidirectional"))
    )
    (net (code "71") (name "unconnected-(IC5-GPIO_07-Pad21)") (class "Default")
      (node (ref "IC5") (pin "21") (pinfunction "GPIO_07_21") (pintype "bidirectional"))
    )
    (net (code "72") (name "unconnected-(IC5-GPIO_17-Pad26)") (class "Default")
      (node (ref "IC5") (pin "26") (pinfunction "GPIO_17_26") (pintype "bidirectional"))
    )
    (net (code "73") (name "unconnected-(IC5-KEYPAD_0-Pad29)") (class "Default")
      (node (ref "IC5") (pin "29") (pinfunction "KEYPAD_0_29") (pintype "passive"))
    )
    (net (code "74") (name "unconnected-(IC5-KEYPAD_1-Pad33)") (class "Default")
      (node (ref "IC5") (pin "33") (pinfunction "KEYPAD_1_33") (pintype "passive"))
    )
    (net (code "75") (name "unconnected-(IC5-KEYPAD_2-Pad30)") (class "Default")
      (node (ref "IC5") (pin "30") (pinfunction "KEYPAD_2_30") (pintype "passive"))
    )
    (net (code "76") (name "unconnected-(IC5-KEYPAD_3-Pad35)") (class "Default")
      (node (ref "IC5") (pin "35") (pinfunction "KEYPAD_3_35") (pintype "passive"))
    )
    (net (code "77") (name "unconnected-(IC5-KEYPAD_4-Pad34)") (class "Default")
      (node (ref "IC5") (pin "34") (pinfunction "KEYPAD_4_34") (pintype "passive"))
    )
    (net (code "78") (name "unconnected-(IC5-KEYSENSE_N0-Pad28)") (class "Default")
      (node (ref "IC5") (pin "28") (pinfunction "KEYSENSE_N0_28") (pintype "passive"))
    )
    (net (code "79") (name "unconnected-(IC5-KEYSENSE_N1-Pad27)") (class "Default")
      (node (ref "IC5") (pin "27") (pinfunction "KEYSENSE_N1_27") (pintype "passive"))
    )
    (net (code "80") (name "unconnected-(IC5-KEYSENSE_N2-Pad31)") (class "Default")
      (node (ref "IC5") (pin "31") (pinfunction "KEYSENSE_N2_31") (pintype "passive"))
    )
    (net (code "81") (name "unconnected-(IC5-KEYSENSE_N3-Pad32)") (class "Default")
      (node (ref "IC5") (pin "32") (pinfunction "KEYSENSE_N3_32") (pintype "passive"))
    )
    (net (code "82") (name "unconnected-(IC5-KEYSENSE_N4-Pad36)") (class "Default")
      (node (ref "IC5") (pin "36") (pinfunction "KEYSENSE_N4_36") (pintype "passive"))
    )
    (net (code "83") (name "unconnected-(IC5-MIC1N-Pad24)") (class "Default")
      (node (ref "IC5") (pin "24") (pinfunction "MIC1N_24") (pintype "passive"))
    )
    (net (code "84") (name "unconnected-(IC5-MIC1P-Pad23)") (class "Default")
      (node (ref "IC5") (pin "23") (pinfunction "MIC1P_23") (pintype "passive"))
    )
    (net (code "85") (name "unconnected-(IC5-PCM_CLK-Pad76)") (class "Default")
      (node (ref "IC5") (pin "76") (pinfunction "PCM_CLK_76") (pintype "passive"))
    )
    (net (code "86") (name "unconnected-(IC5-PCM_DIN-Pad74)") (class "Default")
      (node (ref "IC5") (pin "74") (pinfunction "PCM_DIN_74") (pintype "passive"))
    )
    (net (code "87") (name "unconnected-(IC5-PCM_DOUT-Pad73)") (class "Default")
      (node (ref "IC5") (pin "73") (pinfunction "PCM_DOUT_73") (pintype "passive"))
    )
    (net (code "88") (name "unconnected-(IC5-PCM_SYNC-Pad75)") (class "Default")
      (node (ref "IC5") (pin "75") (pinfunction "PCM_SYNC_75") (pintype "passive"))
    )
    (net (code "89") (name "unconnected-(IC5-RESERVED-Pad15)") (class "Default")
      (node (ref "IC5") (pin "15") (pinfunction "RESERVED_15") (pintype "passive"))
    )
    (net (code "90") (name "unconnected-(IC5-RESERVED-Pad16)") (class "Default")
      (node (ref "IC5") (pin "16") (pinfunction "RESERVED_16") (pintype "passive"))
    )
    (net (code "91") (name "unconnected-(IC5-SPI_CLK-Pad11)") (class "Default")
      (node (ref "IC5") (pin "11") (pinfunction "SPI_CLK_11") (pintype "bidirectional"))
    )
    (net (code "92") (name "unconnected-(IC5-SPI_CS-Pad12)") (class "Default")
      (node (ref "IC5") (pin "12") (pinfunction "SPI_CS_12") (pintype "bidirectional"))
    )
    (net (code "93") (name "unconnected-(IC5-SPI_MISO-Pad14)") (class "Default")
      (node (ref "IC5") (pin "14") (pinfunction "SPI_MISO_14") (pintype "output"))
    )
    (net (code "94") (name "unconnected-(IC5-SPI_MOSI-Pad13)") (class "Default")
      (node (ref "IC5") (pin "13") (pinfunction "SPI_MOSI_13") (pintype "output"))
    )
    (net (code "95") (name "unconnected-(IC5-SPK_M-Pad21)") (class "Default")
      (node (ref "IC5") (pin "21") (pinfunction "SPK_M_21") (pintype "passive"))
    )
    (net (code "96") (name "unconnected-(IC5-SPK_P-Pad22)") (class "Default")
      (node (ref "IC5") (pin "22") (pinfunction "SPK_P_22") (pintype "passive"))
    )
    (net (code "97") (name "unconnected-(IC5-USIM_DET-Pad34)") (class "Default")
      (node (ref "IC5") (pin "34") (pinfunction "USIM_DET_34") (pintype "output"))
    )
    (net (code "98") (name "unconnected-(IC5-WAKE_UP-Pad3)") (class "Default")
      (node (ref "IC5") (pin "3") (pinfunction "WAKE_UP_3") (pintype "bidirectional"))
    )
    (net (code "99") (name "unconnected-(IC6-IO3-Pad4)") (class "Default")
      (node (ref "IC6") (pin "4") (pinfunction "IO3_4") (pintype "passive"))
    )
    (net (code "100") (name "unconnected-(J2-P4-Pad4)") (class "Default")
      (node (ref "J2") (pin "4") (pinfunction "P4_4") (pintype "passive"))
    )
    (net (code "101") (name "unconnected-(SIM1-PRENSENCE-Pad4)") (class "Default")
      (node (ref "SIM1") (pin "4") (pinfunction "PRENSENCE_4") (pintype "passive"))
    )
    (net (code "102") (name "unconnected-(SIM1-VPP-Pad6)") (class "Default")
      (node (ref "SIM1") (pin "6") (pinfunction "VPP_6") (pintype "passive"))
    )
    (net (code "103") (name "unconnected-(U3-R232-Pad15)") (class "Default")
      (node (ref "U3") (pin "15") (pinfunction "R232_15") (pintype "bidirectional"))
    )
    (net (code "104") (name "unconnected-(U3-~{CTS}-Pad9)") (class "Default")
      (node (ref "U3") (pin "9") (pinfunction "~{CTS}_9") (pintype "bidirectional"))
    )
    (net (code "105") (name "unconnected-(U3-~{DCD}-Pad12)") (class "Default")
      (node (ref "U3") (pin "12") (pinfunction "~{DCD}_12") (pintype "bidirectional"))
    )
    (net (code "106") (name "unconnected-(U3-~{DSR}-Pad10)") (class "Default")
      (node (ref "U3") (pin "10") (pinfunction "~{DSR}_10") (pintype "bidirectional"))
    )
    (net (code "107") (name "unconnected-(U3-~{DTR}-Pad13)") (class "Default")
      (node (ref "U3") (pin "13") (pinfunction "~{DTR}_13") (pintype "bidirectional"))
    )
    (net (code "108") (name "unconnected-(U3-~{RI}-Pad11)") (class "Default")
      (node (ref "U3") (pin "11") (pinfunction "~{RI}_11") (pintype "bidirectional"))
    )
    (net (code "109") (name "unconnected-(U3-~{RTS}-Pad14)") (class "Default")
      (node (ref "U3") (pin "14") (pinfunction "~{RTS}_14") (pintype "bidirectional"))
    )
    (net (code "110") (name "unconnected-(y1-P4-Pad4)") (class "Default")
      (node (ref "y1") (pin "4") (pinfunction "P4_4") (pintype "passive+no_connect"))
    )
  )
)
